# board.net
KiCad netlist of a schematic drawn in EAGLE
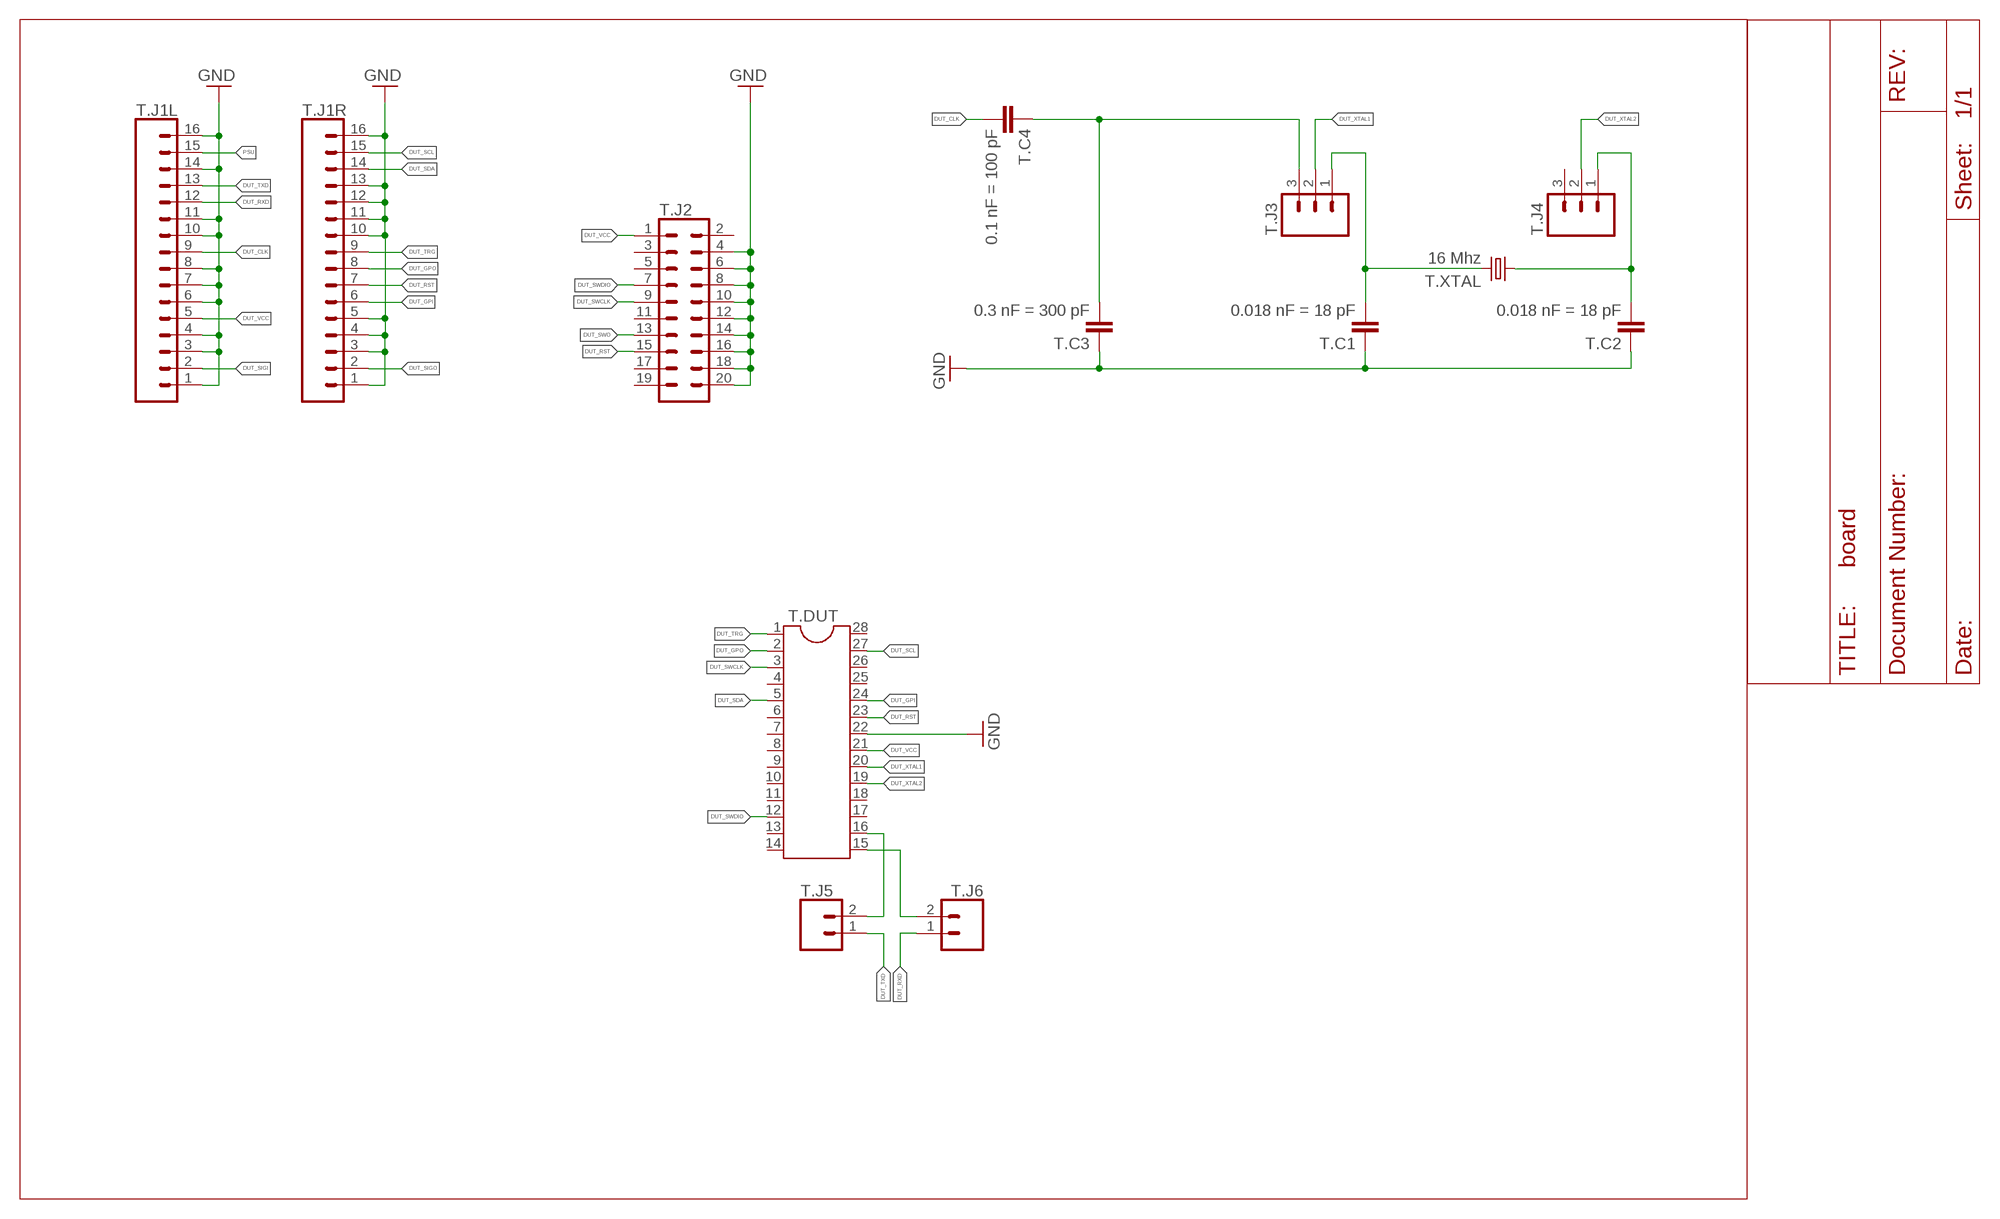
[diagram p0: schematic, sheet 1]

(export (version "E")
  (design (tool "Eeschema 10.0.6"))
  (components
    (comp (ref "T.C1")
      (value "0.018 nF = 18 pF")
      (footprint "eagle-import:0603-CAP")
      (libsource (lib "eagle-import") (part "CAP0603-CAP"))
    )
    (comp (ref "T.C2")
      (value "0.018 nF = 18 pF")
      (footprint "eagle-import:0603-CAP")
      (libsource (lib "eagle-import") (part "CAP0603-CAP"))
    )
    (comp (ref "T.C3")
      (value "0.3 nF = 300 pF")
      (footprint "eagle-import:0603-CAP")
      (libsource (lib "eagle-import") (part "CAP0603-CAP"))
    )
    (comp (ref "T.C4")
      (value "0.1 nF = 100 pF")
      (footprint "eagle-import:0603-CAP")
      (libsource (lib "eagle-import") (part "CAP0603-CAP"))
    )
    (comp (ref "T.DUT")
      (value "DIL28")
      (footprint "eagle-import:DIL28-6")
      (libsource (lib "eagle-import") (part "DIL28"))
    )
    (comp (ref "T.J1L")
      (value "CONN_16")
      (footprint "eagle-import:1X16")
      (libsource (lib "eagle-import") (part "CONN_16"))
    )
    (comp (ref "T.J1R")
      (value "CONN_16")
      (footprint "eagle-import:1X16")
      (libsource (lib "eagle-import") (part "CONN_16"))
    )
    (comp (ref "T.J2")
      (value "CONN_10X2")
      (footprint "eagle-import:2X10")
      (libsource (lib "eagle-import") (part "CONN_10X2"))
    )
    (comp (ref "T.J3")
      (value "M03PTH")
      (footprint "eagle-import:1X03")
      (libsource (lib "eagle-import") (part "M03PTH"))
    )
    (comp (ref "T.J4")
      (value "M03PTH")
      (footprint "eagle-import:1X03")
      (libsource (lib "eagle-import") (part "M03PTH"))
    )
    (comp (ref "T.J5")
      (value "CONN_02")
      (footprint "eagle-import:1X02")
      (libsource (lib "eagle-import") (part "CONN_02"))
    )
    (comp (ref "T.J6")
      (value "CONN_02")
      (footprint "eagle-import:1X02")
      (libsource (lib "eagle-import") (part "CONN_02"))
    )
    (comp (ref "T.XTAL")
      (value "16 Mhz")
      (footprint "eagle-import:HC49US")
      (libsource (lib "eagle-import") (part "CRYSTALHC49US"))
    )
  )
  (nets
    (net (code "1") (name "DUT_CLK") (class "Default")
      (node (ref "T.C4") (pin "2") (pinfunction "2_2") (pintype "passive"))
      (node (ref "T.J1L") (pin "9") (pinfunction "9_9") (pintype "passive"))
    )
    (net (code "2") (name "DUT_GPI") (class "Default")
      (node (ref "T.DUT") (pin "24") (pinfunction "24_24") (pintype "passive"))
      (node (ref "T.J1R") (pin "6") (pinfunction "6_6") (pintype "passive"))
    )
    (net (code "3") (name "DUT_GPO") (class "Default")
      (node (ref "T.DUT") (pin "2") (pinfunction "2_2") (pintype "passive"))
      (node (ref "T.J1R") (pin "8") (pinfunction "8_8") (pintype "passive"))
    )
    (net (code "4") (name "DUT_RST") (class "Default")
      (node (ref "T.DUT") (pin "23") (pinfunction "23_23") (pintype "passive"))
      (node (ref "T.J1R") (pin "7") (pinfunction "7_7") (pintype "passive"))
      (node (ref "T.J2") (pin "15") (pinfunction "15_15") (pintype "passive"))
    )
    (net (code "5") (name "DUT_RXD") (class "Default")
      (node (ref "T.J1L") (pin "12") (pinfunction "12_12") (pintype "passive"))
      (node (ref "T.J6") (pin "1") (pinfunction "1_1") (pintype "passive"))
    )
    (net (code "6") (name "DUT_SCL") (class "Default")
      (node (ref "T.DUT") (pin "27") (pinfunction "27_27") (pintype "passive"))
      (node (ref "T.J1R") (pin "15") (pinfunction "15_15") (pintype "passive"))
    )
    (net (code "7") (name "DUT_SDA") (class "Default")
      (node (ref "T.DUT") (pin "5") (pinfunction "5_5") (pintype "passive"))
      (node (ref "T.J1R") (pin "14") (pinfunction "14_14") (pintype "passive"))
    )
    (net (code "8") (name "DUT_SIGI") (class "Default")
      (node (ref "T.J1L") (pin "2") (pinfunction "2_2") (pintype "passive"))
    )
    (net (code "9") (name "DUT_SIGO") (class "Default")
      (node (ref "T.J1R") (pin "2") (pinfunction "2_2") (pintype "passive"))
    )
    (net (code "10") (name "DUT_SWCLK") (class "Default")
      (node (ref "T.DUT") (pin "3") (pinfunction "3_3") (pintype "passive"))
      (node (ref "T.J2") (pin "9") (pinfunction "9_9") (pintype "passive"))
    )
    (net (code "11") (name "DUT_SWDIO") (class "Default")
      (node (ref "T.DUT") (pin "12") (pinfunction "12_12") (pintype "passive"))
      (node (ref "T.J2") (pin "7") (pinfunction "7_7") (pintype "passive"))
    )
    (net (code "12") (name "DUT_SWO") (class "Default")
      (node (ref "T.J2") (pin "13") (pinfunction "13_13") (pintype "passive"))
    )
    (net (code "13") (name "DUT_TRG") (class "Default")
      (node (ref "T.DUT") (pin "1") (pinfunction "1_1") (pintype "passive"))
      (node (ref "T.J1R") (pin "9") (pinfunction "9_9") (pintype "passive"))
    )
    (net (code "14") (name "DUT_TXD") (class "Default")
      (node (ref "T.J1L") (pin "13") (pinfunction "13_13") (pintype "passive"))
      (node (ref "T.J5") (pin "1") (pinfunction "1_1") (pintype "passive"))
    )
    (net (code "15") (name "DUT_VCC") (class "Default")
      (node (ref "T.DUT") (pin "21") (pinfunction "21_21") (pintype "passive"))
      (node (ref "T.J1L") (pin "5") (pinfunction "5_5") (pintype "passive"))
      (node (ref "T.J2") (pin "1") (pinfunction "1_1") (pintype "passive"))
    )
    (net (code "16") (name "DUT_XTAL1") (class "Default")
      (node (ref "T.DUT") (pin "20") (pinfunction "20_20") (pintype "passive"))
      (node (ref "T.J3") (pin "2") (pinfunction "2_2") (pintype "passive"))
    )
    (net (code "17") (name "DUT_XTAL2") (class "Default")
      (node (ref "T.DUT") (pin "19") (pinfunction "19_19") (pintype "passive"))
      (node (ref "T.J4") (pin "2") (pinfunction "2_2") (pintype "passive"))
    )
    (net (code "18") (name "GND") (class "Default")
      (node (ref "T.C1") (pin "1") (pinfunction "1_1") (pintype "passive"))
      (node (ref "T.C2") (pin "1") (pinfunction "1_1") (pintype "passive"))
      (node (ref "T.C3") (pin "1") (pinfunction "1_1") (pintype "passive"))
      (node (ref "T.DUT") (pin "22") (pinfunction "22_22") (pintype "passive"))
      (node (ref "T.J1L") (pin "1") (pinfunction "1_1") (pintype "passive"))
      (node (ref "T.J1L") (pin "10") (pinfunction "10_10") (pintype "passive"))
      (node (ref "T.J1L") (pin "11") (pinfunction "11_11") (pintype "passive"))
      (node (ref "T.J1L") (pin "14") (pinfunction "14_14") (pintype "passive"))
      (node (ref "T.J1L") (pin "16") (pinfunction "16_16") (pintype "passive"))
      (node (ref "T.J1L") (pin "3") (pinfunction "3_3") (pintype "passive"))
      (node (ref "T.J1L") (pin "4") (pinfunction "4_4") (pintype "passive"))
      (node (ref "T.J1L") (pin "6") (pinfunction "6_6") (pintype "passive"))
      (node (ref "T.J1L") (pin "7") (pinfunction "7_7") (pintype "passive"))
      (node (ref "T.J1L") (pin "8") (pinfunction "8_8") (pintype "passive"))
      (node (ref "T.J1R") (pin "1") (pinfunction "1_1") (pintype "passive"))
      (node (ref "T.J1R") (pin "10") (pinfunction "10_10") (pintype "passive"))
      (node (ref "T.J1R") (pin "11") (pinfunction "11_11") (pintype "passive"))
      (node (ref "T.J1R") (pin "12") (pinfunction "12_12") (pintype "passive"))
      (node (ref "T.J1R") (pin "13") (pinfunction "13_13") (pintype "passive"))
      (node (ref "T.J1R") (pin "16") (pinfunction "16_16") (pintype "passive"))
      (node (ref "T.J1R") (pin "3") (pinfunction "3_3") (pintype "passive"))
      (node (ref "T.J1R") (pin "4") (pinfunction "4_4") (pintype "passive"))
      (node (ref "T.J1R") (pin "5") (pinfunction "5_5") (pintype "passive"))
      (node (ref "T.J2") (pin "10") (pinfunction "10_10") (pintype "passive"))
      (node (ref "T.J2") (pin "12") (pinfunction "12_12") (pintype "passive"))
      (node (ref "T.J2") (pin "14") (pinfunction "14_14") (pintype "passive"))
      (node (ref "T.J2") (pin "16") (pinfunction "16_16") (pintype "passive"))
      (node (ref "T.J2") (pin "18") (pinfunction "18_18") (pintype "passive"))
      (node (ref "T.J2") (pin "20") (pinfunction "20_20") (pintype "passive"))
      (node (ref "T.J2") (pin "4") (pinfunction "4_4") (pintype "passive"))
      (node (ref "T.J2") (pin "6") (pinfunction "6_6") (pintype "passive"))
      (node (ref "T.J2") (pin "8") (pinfunction "8_8") (pintype "passive"))
    )
    (net (code "19") (name "Net-(T.C1-Pad2)") (class "Default")
      (node (ref "T.C1") (pin "2") (pinfunction "2_2") (pintype "passive"))
      (node (ref "T.J3") (pin "1") (pinfunction "1_1") (pintype "passive"))
      (node (ref "T.XTAL") (pin "2") (pinfunction "2_2") (pintype "passive"))
    )
    (net (code "20") (name "Net-(T.C2-Pad2)") (class "Default")
      (node (ref "T.C2") (pin "2") (pinfunction "2_2") (pintype "passive"))
      (node (ref "T.J4") (pin "1") (pinfunction "1_1") (pintype "passive"))
      (node (ref "T.XTAL") (pin "1") (pinfunction "1_1") (pintype "passive"))
    )
    (net (code "21") (name "Net-(T.C3-Pad2)") (class "Default")
      (node (ref "T.C3") (pin "2") (pinfunction "2_2") (pintype "passive"))
      (node (ref "T.C4") (pin "1") (pinfunction "1_1") (pintype "passive"))
      (node (ref "T.J3") (pin "3") (pinfunction "3_3") (pintype "passive"))
    )
    (net (code "22") (name "Net-(T.DUT-Pad15)") (class "Default")
      (node (ref "T.DUT") (pin "15") (pinfunction "15_15") (pintype "passive"))
      (node (ref "T.J6") (pin "2") (pinfunction "2_2") (pintype "passive"))
    )
    (net (code "23") (name "Net-(T.DUT-Pad16)") (class "Default")
      (node (ref "T.DUT") (pin "16") (pinfunction "16_16") (pintype "passive"))
      (node (ref "T.J5") (pin "2") (pinfunction "2_2") (pintype "passive"))
    )
    (net (code "24") (name "PSU") (class "Default")
      (node (ref "T.J1L") (pin "15") (pinfunction "15_15") (pintype "passive"))
    )
    (net (code "25") (name "unconnected-(T.DUT-Pad4)") (class "Default")
      (node (ref "T.DUT") (pin "4") (pinfunction "4_4") (pintype "passive"))
    )
    (net (code "26") (name "unconnected-(T.DUT-Pad6)") (class "Default")
      (node (ref "T.DUT") (pin "6") (pinfunction "6_6") (pintype "passive"))
    )
    (net (code "27") (name "unconnected-(T.DUT-Pad7)") (class "Default")
      (node (ref "T.DUT") (pin "7") (pinfunction "7_7") (pintype "passive"))
    )
    (net (code "28") (name "unconnected-(T.DUT-Pad8)") (class "Default")
      (node (ref "T.DUT") (pin "8") (pinfunction "8_8") (pintype "passive"))
    )
    (net (code "29") (name "unconnected-(T.DUT-Pad9)") (class "Default")
      (node (ref "T.DUT") (pin "9") (pinfunction "9_9") (pintype "passive"))
    )
    (net (code "30") (name "unconnected-(T.DUT-Pad10)") (class "Default")
      (node (ref "T.DUT") (pin "10") (pinfunction "10_10") (pintype "passive"))
    )
    (net (code "31") (name "unconnected-(T.DUT-Pad11)") (class "Default")
      (node (ref "T.DUT") (pin "11") (pinfunction "11_11") (pintype "passive"))
    )
    (net (code "32") (name "unconnected-(T.DUT-Pad13)") (class "Default")
      (node (ref "T.DUT") (pin "13") (pinfunction "13_13") (pintype "passive"))
    )
    (net (code "33") (name "unconnected-(T.DUT-Pad14)") (class "Default")
      (node (ref "T.DUT") (pin "14") (pinfunction "14_14") (pintype "passive"))
    )
    (net (code "34") (name "unconnected-(T.DUT-Pad17)") (class "Default")
      (node (ref "T.DUT") (pin "17") (pinfunction "17_17") (pintype "passive"))
    )
    (net (code "35") (name "unconnected-(T.DUT-Pad18)") (class "Default")
      (node (ref "T.DUT") (pin "18") (pinfunction "18_18") (pintype "passive"))
    )
    (net (code "36") (name "unconnected-(T.DUT-Pad25)") (class "Default")
      (node (ref "T.DUT") (pin "25") (pinfunction "25_25") (pintype "passive"))
    )
    (net (code "37") (name "unconnected-(T.DUT-Pad26)") (class "Default")
      (node (ref "T.DUT") (pin "26") (pinfunction "26_26") (pintype "passive"))
    )
    (net (code "38") (name "unconnected-(T.DUT-Pad28)") (class "Default")
      (node (ref "T.DUT") (pin "28") (pinfunction "28_28") (pintype "passive"))
    )
    (net (code "39") (name "unconnected-(T.J2-Pad2)") (class "Default")
      (node (ref "T.J2") (pin "2") (pinfunction "2_2") (pintype "passive"))
    )
    (net (code "40") (name "unconnected-(T.J2-Pad3)") (class "Default")
      (node (ref "T.J2") (pin "3") (pinfunction "3_3") (pintype "passive"))
    )
    (net (code "41") (name "unconnected-(T.J2-Pad5)") (class "Default")
      (node (ref "T.J2") (pin "5") (pinfunction "5_5") (pintype "passive"))
    )
    (net (code "42") (name "unconnected-(T.J2-Pad11)") (class "Default")
      (node (ref "T.J2") (pin "11") (pinfunction "11_11") (pintype "passive"))
    )
    (net (code "43") (name "unconnected-(T.J2-Pad17)") (class "Default")
      (node (ref "T.J2") (pin "17") (pinfunction "17_17") (pintype "passive"))
    )
    (net (code "44") (name "unconnected-(T.J2-Pad19)") (class "Default")
      (node (ref "T.J2") (pin "19") (pinfunction "19_19") (pintype "passive"))
    )
    (net (code "45") (name "unconnected-(T.J4-Pad3)") (class "Default")
      (node (ref "T.J4") (pin "3") (pinfunction "3_3") (pintype "passive"))
    )
  )
)
